# ADC5G_POWER.net
KiCad netlist of a schematic drawn in Altium Designer
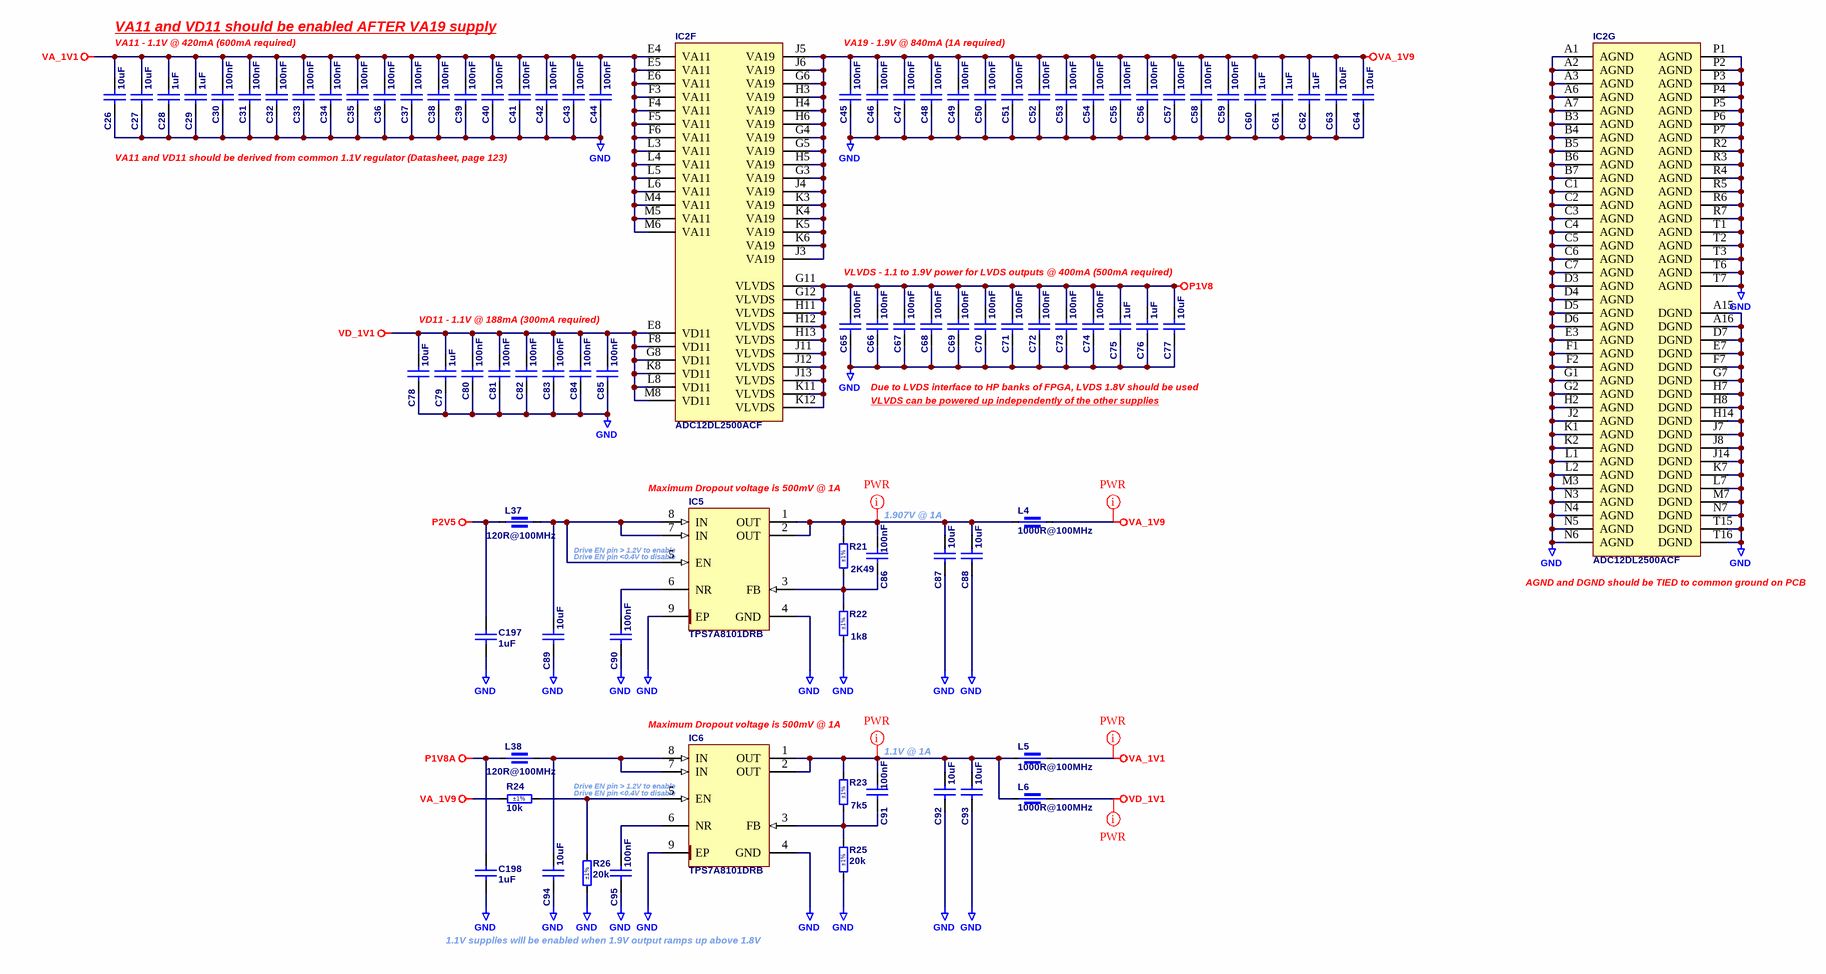
[diagram p0: ADC5G_POWER.SchDoc]

(export (version "E")
  (design (tool "Eeschema 10.0.6"))
  (components
    (comp (ref "C26")
      (value "10uF")
      (footprint "CAPC1608X90N")
      (description "Non-polarised capacitor")
      (fields
        (field (name "PART NUMBER") "CC0603_10UF_16V_10%_X5R_MURATA_GRT188R61C106KE13")
        (field (name "VOLTAGE") "16V")
        (field (name "AUTHOR") "CERN DEM HF")
      )
      (libsource (lib "Capacitors") (part "Capacitor - non polarized"))
    )
    (comp (ref "C27")
      (value "10uF")
      (footprint "CAPC1608X90N")
      (description "Non-polarised capacitor")
      (fields
        (field (name "PART NUMBER") "CC0603_10UF_16V_10%_X5R_MURATA_GRT188R61C106KE13")
        (field (name "VOLTAGE") "16V")
        (field (name "AUTHOR") "CERN DEM HF")
      )
      (libsource (lib "Capacitors") (part "Capacitor - non polarized"))
    )
    (comp (ref "C28")
      (value "1uF")
      (footprint "CAPC1005X55N")
      (description "Non-polarised capacitor")
      (fields
        (field (name "PART NUMBER") "CC0402_1UF_16V_10%_X5R")
        (field (name "VOLTAGE") "16V")
        (field (name "AUTHOR") "CERN DEM JLC")
      )
      (libsource (lib "Capacitors") (part "Capacitor - non polarized"))
    )
    (comp (ref "C29")
      (value "1uF")
      (footprint "CAPC1005X55N")
      (description "Non-polarised capacitor")
      (fields
        (field (name "PART NUMBER") "CC0402_1UF_16V_10%_X5R")
        (field (name "VOLTAGE") "16V")
        (field (name "AUTHOR") "CERN DEM JLC")
      )
      (libsource (lib "Capacitors") (part "Capacitor - non polarized"))
    )
    (comp (ref "C30")
      (value "100nF")
      (footprint "CAPC0603X33N")
      (description "Non-polarised capacitor")
      (fields
        (field (name "PART NUMBER") "CC0201_100NF_6.3V_10%_X7R")
        (field (name "VOLTAGE") "6.3V")
        (field (name "AUTHOR") "CERN DEM BC")
      )
      (libsource (lib "Capacitors") (part "Capacitor - non polarized"))
    )
    (comp (ref "C31")
      (value "100nF")
      (footprint "CAPC0603X33N")
      (description "Non-polarised capacitor")
      (fields
        (field (name "PART NUMBER") "CC0201_100NF_6.3V_10%_X7R")
        (field (name "VOLTAGE") "6.3V")
        (field (name "AUTHOR") "CERN DEM BC")
      )
      (libsource (lib "Capacitors") (part "Capacitor - non polarized"))
    )
    (comp (ref "C32")
      (value "100nF")
      (footprint "CAPC0603X33N")
      (description "Non-polarised capacitor")
      (fields
        (field (name "PART NUMBER") "CC0201_100NF_6.3V_10%_X7R")
        (field (name "VOLTAGE") "6.3V")
        (field (name "AUTHOR") "CERN DEM BC")
      )
      (libsource (lib "Capacitors") (part "Capacitor - non polarized"))
    )
    (comp (ref "C33")
      (value "100nF")
      (footprint "CAPC0603X33N")
      (description "Non-polarised capacitor")
      (fields
        (field (name "PART NUMBER") "CC0201_100NF_6.3V_10%_X7R")
        (field (name "VOLTAGE") "6.3V")
        (field (name "AUTHOR") "CERN DEM BC")
      )
      (libsource (lib "Capacitors") (part "Capacitor - non polarized"))
    )
    (comp (ref "C34")
      (value "100nF")
      (footprint "CAPC0603X33N")
      (description "Non-polarised capacitor")
      (fields
        (field (name "PART NUMBER") "CC0201_100NF_6.3V_10%_X7R")
        (field (name "VOLTAGE") "6.3V")
        (field (name "AUTHOR") "CERN DEM BC")
      )
      (libsource (lib "Capacitors") (part "Capacitor - non polarized"))
    )
    (comp (ref "C35")
      (value "100nF")
      (footprint "CAPC0603X33N")
      (description "Non-polarised capacitor")
      (fields
        (field (name "PART NUMBER") "CC0201_100NF_6.3V_10%_X7R")
        (field (name "VOLTAGE") "6.3V")
        (field (name "AUTHOR") "CERN DEM BC")
      )
      (libsource (lib "Capacitors") (part "Capacitor - non polarized"))
    )
    (comp (ref "C36")
      (value "100nF")
      (footprint "CAPC0603X33N")
      (description "Non-polarised capacitor")
      (fields
        (field (name "PART NUMBER") "CC0201_100NF_6.3V_10%_X7R")
        (field (name "VOLTAGE") "6.3V")
        (field (name "AUTHOR") "CERN DEM BC")
      )
      (libsource (lib "Capacitors") (part "Capacitor - non polarized"))
    )
    (comp (ref "C37")
      (value "100nF")
      (footprint "CAPC0603X33N")
      (description "Non-polarised capacitor")
      (fields
        (field (name "PART NUMBER") "CC0201_100NF_6.3V_10%_X7R")
        (field (name "VOLTAGE") "6.3V")
        (field (name "AUTHOR") "CERN DEM BC")
      )
      (libsource (lib "Capacitors") (part "Capacitor - non polarized"))
    )
    (comp (ref "C38")
      (value "100nF")
      (footprint "CAPC0603X33N")
      (description "Non-polarised capacitor")
      (fields
        (field (name "PART NUMBER") "CC0201_100NF_6.3V_10%_X7R")
        (field (name "VOLTAGE") "6.3V")
        (field (name "AUTHOR") "CERN DEM BC")
      )
      (libsource (lib "Capacitors") (part "Capacitor - non polarized"))
    )
    (comp (ref "C39")
      (value "100nF")
      (footprint "CAPC0603X33N")
      (description "Non-polarised capacitor")
      (fields
        (field (name "PART NUMBER") "CC0201_100NF_6.3V_10%_X7R")
        (field (name "VOLTAGE") "6.3V")
        (field (name "AUTHOR") "CERN DEM BC")
      )
      (libsource (lib "Capacitors") (part "Capacitor - non polarized"))
    )
    (comp (ref "C40")
      (value "100nF")
      (footprint "CAPC0603X33N")
      (description "Non-polarised capacitor")
      (fields
        (field (name "PART NUMBER") "CC0201_100NF_6.3V_10%_X7R")
        (field (name "VOLTAGE") "6.3V")
        (field (name "AUTHOR") "CERN DEM BC")
      )
      (libsource (lib "Capacitors") (part "Capacitor - non polarized"))
    )
    (comp (ref "C41")
      (value "100nF")
      (footprint "CAPC0603X33N")
      (description "Non-polarised capacitor")
      (fields
        (field (name "PART NUMBER") "CC0201_100NF_6.3V_10%_X7R")
        (field (name "VOLTAGE") "6.3V")
        (field (name "AUTHOR") "CERN DEM BC")
      )
      (libsource (lib "Capacitors") (part "Capacitor - non polarized"))
    )
    (comp (ref "C42")
      (value "100nF")
      (footprint "CAPC0603X33N")
      (description "Non-polarised capacitor")
      (fields
        (field (name "PART NUMBER") "CC0201_100NF_6.3V_10%_X7R")
        (field (name "VOLTAGE") "6.3V")
        (field (name "AUTHOR") "CERN DEM BC")
      )
      (libsource (lib "Capacitors") (part "Capacitor - non polarized"))
    )
    (comp (ref "C43")
      (value "100nF")
      (footprint "CAPC0603X33N")
      (description "Non-polarised capacitor")
      (fields
        (field (name "PART NUMBER") "CC0201_100NF_6.3V_10%_X7R")
        (field (name "VOLTAGE") "6.3V")
        (field (name "AUTHOR") "CERN DEM BC")
      )
      (libsource (lib "Capacitors") (part "Capacitor - non polarized"))
    )
    (comp (ref "C44")
      (value "100nF")
      (footprint "CAPC0603X33N")
      (description "Non-polarised capacitor")
      (fields
        (field (name "PART NUMBER") "CC0201_100NF_6.3V_10%_X7R")
        (field (name "VOLTAGE") "6.3V")
        (field (name "AUTHOR") "CERN DEM BC")
      )
      (libsource (lib "Capacitors") (part "Capacitor - non polarized"))
    )
    (comp (ref "C45")
      (value "100nF")
      (footprint "CAPC0603X33N")
      (description "Non-polarised capacitor")
      (fields
        (field (name "PART NUMBER") "CC0201_100NF_6.3V_10%_X7R")
        (field (name "VOLTAGE") "6.3V")
        (field (name "AUTHOR") "CERN DEM BC")
      )
      (libsource (lib "Capacitors") (part "Capacitor - non polarized"))
    )
    (comp (ref "C46")
      (value "100nF")
      (footprint "CAPC0603X33N")
      (description "Non-polarised capacitor")
      (fields
        (field (name "PART NUMBER") "CC0201_100NF_6.3V_10%_X7R")
        (field (name "VOLTAGE") "6.3V")
        (field (name "AUTHOR") "CERN DEM BC")
      )
      (libsource (lib "Capacitors") (part "Capacitor - non polarized"))
    )
    (comp (ref "C47")
      (value "100nF")
      (footprint "CAPC0603X33N")
      (description "Non-polarised capacitor")
      (fields
        (field (name "PART NUMBER") "CC0201_100NF_6.3V_10%_X7R")
        (field (name "VOLTAGE") "6.3V")
        (field (name "AUTHOR") "CERN DEM BC")
      )
      (libsource (lib "Capacitors") (part "Capacitor - non polarized"))
    )
    (comp (ref "C48")
      (value "100nF")
      (footprint "CAPC0603X33N")
      (description "Non-polarised capacitor")
      (fields
        (field (name "PART NUMBER") "CC0201_100NF_6.3V_10%_X7R")
        (field (name "VOLTAGE") "6.3V")
        (field (name "AUTHOR") "CERN DEM BC")
      )
      (libsource (lib "Capacitors") (part "Capacitor - non polarized"))
    )
    (comp (ref "C49")
      (value "100nF")
      (footprint "CAPC0603X33N")
      (description "Non-polarised capacitor")
      (fields
        (field (name "PART NUMBER") "CC0201_100NF_6.3V_10%_X7R")
        (field (name "VOLTAGE") "6.3V")
        (field (name "AUTHOR") "CERN DEM BC")
      )
      (libsource (lib "Capacitors") (part "Capacitor - non polarized"))
    )
    (comp (ref "C50")
      (value "100nF")
      (footprint "CAPC0603X33N")
      (description "Non-polarised capacitor")
      (fields
        (field (name "PART NUMBER") "CC0201_100NF_6.3V_10%_X7R")
        (field (name "VOLTAGE") "6.3V")
        (field (name "AUTHOR") "CERN DEM BC")
      )
      (libsource (lib "Capacitors") (part "Capacitor - non polarized"))
    )
    (comp (ref "C51")
      (value "100nF")
      (footprint "CAPC0603X33N")
      (description "Non-polarised capacitor")
      (fields
        (field (name "PART NUMBER") "CC0201_100NF_6.3V_10%_X7R")
        (field (name "VOLTAGE") "6.3V")
        (field (name "AUTHOR") "CERN DEM BC")
      )
      (libsource (lib "Capacitors") (part "Capacitor - non polarized"))
    )
    (comp (ref "C52")
      (value "100nF")
      (footprint "CAPC0603X33N")
      (description "Non-polarised capacitor")
      (fields
        (field (name "PART NUMBER") "CC0201_100NF_6.3V_10%_X7R")
        (field (name "VOLTAGE") "6.3V")
        (field (name "AUTHOR") "CERN DEM BC")
      )
      (libsource (lib "Capacitors") (part "Capacitor - non polarized"))
    )
    (comp (ref "C53")
      (value "100nF")
      (footprint "CAPC0603X33N")
      (description "Non-polarised capacitor")
      (fields
        (field (name "PART NUMBER") "CC0201_100NF_6.3V_10%_X7R")
        (field (name "VOLTAGE") "6.3V")
        (field (name "AUTHOR") "CERN DEM BC")
      )
      (libsource (lib "Capacitors") (part "Capacitor - non polarized"))
    )
    (comp (ref "C54")
      (value "100nF")
      (footprint "CAPC0603X33N")
      (description "Non-polarised capacitor")
      (fields
        (field (name "PART NUMBER") "CC0201_100NF_6.3V_10%_X7R")
        (field (name "VOLTAGE") "6.3V")
        (field (name "AUTHOR") "CERN DEM BC")
      )
      (libsource (lib "Capacitors") (part "Capacitor - non polarized"))
    )
    (comp (ref "C55")
      (value "100nF")
      (footprint "CAPC0603X33N")
      (description "Non-polarised capacitor")
      (fields
        (field (name "PART NUMBER") "CC0201_100NF_6.3V_10%_X7R")
        (field (name "VOLTAGE") "6.3V")
        (field (name "AUTHOR") "CERN DEM BC")
      )
      (libsource (lib "Capacitors") (part "Capacitor - non polarized"))
    )
    (comp (ref "C56")
      (value "100nF")
      (footprint "CAPC0603X33N")
      (description "Non-polarised capacitor")
      (fields
        (field (name "PART NUMBER") "CC0201_100NF_6.3V_10%_X7R")
        (field (name "VOLTAGE") "6.3V")
        (field (name "AUTHOR") "CERN DEM BC")
      )
      (libsource (lib "Capacitors") (part "Capacitor - non polarized"))
    )
    (comp (ref "C57")
      (value "100nF")
      (footprint "CAPC0603X33N")
      (description "Non-polarised capacitor")
      (fields
        (field (name "PART NUMBER") "CC0201_100NF_6.3V_10%_X7R")
        (field (name "VOLTAGE") "6.3V")
        (field (name "AUTHOR") "CERN DEM BC")
      )
      (libsource (lib "Capacitors") (part "Capacitor - non polarized"))
    )
    (comp (ref "C58")
      (value "100nF")
      (footprint "CAPC0603X33N")
      (description "Non-polarised capacitor")
      (fields
        (field (name "PART NUMBER") "CC0201_100NF_6.3V_10%_X7R")
        (field (name "VOLTAGE") "6.3V")
        (field (name "AUTHOR") "CERN DEM BC")
      )
      (libsource (lib "Capacitors") (part "Capacitor - non polarized"))
    )
    (comp (ref "C59")
      (value "100nF")
      (footprint "CAPC0603X33N")
      (description "Non-polarised capacitor")
      (fields
        (field (name "PART NUMBER") "CC0201_100NF_6.3V_10%_X7R")
        (field (name "VOLTAGE") "6.3V")
        (field (name "AUTHOR") "CERN DEM BC")
      )
      (libsource (lib "Capacitors") (part "Capacitor - non polarized"))
    )
    (comp (ref "C60")
      (value "1uF")
      (footprint "CAPC1005X55N")
      (description "Non-polarised capacitor")
      (fields
        (field (name "PART NUMBER") "CC0402_1UF_16V_10%_X5R")
        (field (name "VOLTAGE") "16V")
        (field (name "AUTHOR") "CERN DEM JLC")
      )
      (libsource (lib "Capacitors") (part "Capacitor - non polarized"))
    )
    (comp (ref "C61")
      (value "1uF")
      (footprint "CAPC1005X55N")
      (description "Non-polarised capacitor")
      (fields
        (field (name "PART NUMBER") "CC0402_1UF_16V_10%_X5R")
        (field (name "VOLTAGE") "16V")
        (field (name "AUTHOR") "CERN DEM JLC")
      )
      (libsource (lib "Capacitors") (part "Capacitor - non polarized"))
    )
    (comp (ref "C62")
      (value "1uF")
      (footprint "CAPC1005X55N")
      (description "Non-polarised capacitor")
      (fields
        (field (name "PART NUMBER") "CC0402_1UF_16V_10%_X5R")
        (field (name "VOLTAGE") "16V")
        (field (name "AUTHOR") "CERN DEM JLC")
      )
      (libsource (lib "Capacitors") (part "Capacitor - non polarized"))
    )
    (comp (ref "C63")
      (value "10uF")
      (footprint "CAPC1608X90N")
      (description "Non-polarised capacitor")
      (fields
        (field (name "PART NUMBER") "CC0603_10UF_16V_10%_X5R_MURATA_GRT188R61C106KE13")
        (field (name "VOLTAGE") "16V")
        (field (name "AUTHOR") "CERN DEM HF")
      )
      (libsource (lib "Capacitors") (part "Capacitor - non polarized"))
    )
    (comp (ref "C64")
      (value "10uF")
      (footprint "CAPC1608X90N")
      (description "Non-polarised capacitor")
      (fields
        (field (name "PART NUMBER") "CC0603_10UF_16V_10%_X5R_MURATA_GRT188R61C106KE13")
        (field (name "VOLTAGE") "16V")
        (field (name "AUTHOR") "CERN DEM HF")
      )
      (libsource (lib "Capacitors") (part "Capacitor - non polarized"))
    )
    (comp (ref "C65")
      (value "100nF")
      (footprint "CAPC0603X33N")
      (description "Non-polarised capacitor")
      (fields
        (field (name "PART NUMBER") "CC0201_100NF_6.3V_10%_X7R")
        (field (name "VOLTAGE") "6.3V")
        (field (name "AUTHOR") "CERN DEM BC")
      )
      (libsource (lib "Capacitors") (part "Capacitor - non polarized"))
    )
    (comp (ref "C66")
      (value "100nF")
      (footprint "CAPC0603X33N")
      (description "Non-polarised capacitor")
      (fields
        (field (name "PART NUMBER") "CC0201_100NF_6.3V_10%_X7R")
        (field (name "VOLTAGE") "6.3V")
        (field (name "AUTHOR") "CERN DEM BC")
      )
      (libsource (lib "Capacitors") (part "Capacitor - non polarized"))
    )
    (comp (ref "C67")
      (value "100nF")
      (footprint "CAPC0603X33N")
      (description "Non-polarised capacitor")
      (fields
        (field (name "PART NUMBER") "CC0201_100NF_6.3V_10%_X7R")
        (field (name "VOLTAGE") "6.3V")
        (field (name "AUTHOR") "CERN DEM BC")
      )
      (libsource (lib "Capacitors") (part "Capacitor - non polarized"))
    )
    (comp (ref "C68")
      (value "100nF")
      (footprint "CAPC0603X33N")
      (description "Non-polarised capacitor")
      (fields
        (field (name "PART NUMBER") "CC0201_100NF_6.3V_10%_X7R")
        (field (name "VOLTAGE") "6.3V")
        (field (name "AUTHOR") "CERN DEM BC")
      )
      (libsource (lib "Capacitors") (part "Capacitor - non polarized"))
    )
    (comp (ref "C69")
      (value "100nF")
      (footprint "CAPC0603X33N")
      (description "Non-polarised capacitor")
      (fields
        (field (name "PART NUMBER") "CC0201_100NF_6.3V_10%_X7R")
        (field (name "VOLTAGE") "6.3V")
        (field (name "AUTHOR") "CERN DEM BC")
      )
      (libsource (lib "Capacitors") (part "Capacitor - non polarized"))
    )
    (comp (ref "C70")
      (value "100nF")
      (footprint "CAPC0603X33N")
      (description "Non-polarised capacitor")
      (fields
        (field (name "PART NUMBER") "CC0201_100NF_6.3V_10%_X7R")
        (field (name "VOLTAGE") "6.3V")
        (field (name "AUTHOR") "CERN DEM BC")
      )
      (libsource (lib "Capacitors") (part "Capacitor - non polarized"))
    )
    (comp (ref "C71")
      (value "100nF")
      (footprint "CAPC0603X33N")
      (description "Non-polarised capacitor")
      (fields
        (field (name "PART NUMBER") "CC0201_100NF_6.3V_10%_X7R")
        (field (name "VOLTAGE") "6.3V")
        (field (name "AUTHOR") "CERN DEM BC")
      )
      (libsource (lib "Capacitors") (part "Capacitor - non polarized"))
    )
    (comp (ref "C72")
      (value "100nF")
      (footprint "CAPC0603X33N")
      (description "Non-polarised capacitor")
      (fields
        (field (name "PART NUMBER") "CC0201_100NF_6.3V_10%_X7R")
        (field (name "VOLTAGE") "6.3V")
        (field (name "AUTHOR") "CERN DEM BC")
      )
      (libsource (lib "Capacitors") (part "Capacitor - non polarized"))
    )
    (comp (ref "C73")
      (value "100nF")
      (footprint "CAPC0603X33N")
      (description "Non-polarised capacitor")
      (fields
        (field (name "PART NUMBER") "CC0201_100NF_6.3V_10%_X7R")
        (field (name "VOLTAGE") "6.3V")
        (field (name "AUTHOR") "CERN DEM BC")
      )
      (libsource (lib "Capacitors") (part "Capacitor - non polarized"))
    )
    (comp (ref "C74")
      (value "100nF")
      (footprint "CAPC0603X33N")
      (description "Non-polarised capacitor")
      (fields
        (field (name "PART NUMBER") "CC0201_100NF_6.3V_10%_X7R")
        (field (name "VOLTAGE") "6.3V")
        (field (name "AUTHOR") "CERN DEM BC")
      )
      (libsource (lib "Capacitors") (part "Capacitor - non polarized"))
    )
    (comp (ref "C75")
      (value "1uF")
      (footprint "CAPC1005X55N")
      (description "Non-polarised capacitor")
      (fields
        (field (name "PART NUMBER") "CC0402_1UF_16V_10%_X5R")
        (field (name "VOLTAGE") "16V")
        (field (name "AUTHOR") "CERN DEM JLC")
      )
      (libsource (lib "Capacitors") (part "Capacitor - non polarized"))
    )
    (comp (ref "C76")
      (value "1uF")
      (footprint "CAPC1005X55N")
      (description "Non-polarised capacitor")
      (fields
        (field (name "PART NUMBER") "CC0402_1UF_16V_10%_X5R")
        (field (name "VOLTAGE") "16V")
        (field (name "AUTHOR") "CERN DEM JLC")
      )
      (libsource (lib "Capacitors") (part "Capacitor - non polarized"))
    )
    (comp (ref "C77")
      (value "10uF")
      (footprint "CAPC1608X90N")
      (description "Non-polarised capacitor")
      (fields
        (field (name "PART NUMBER") "CC0603_10UF_16V_10%_X5R_MURATA_GRT188R61C106KE13")
        (field (name "VOLTAGE") "16V")
        (field (name "AUTHOR") "CERN DEM HF")
      )
      (libsource (lib "Capacitors") (part "Capacitor - non polarized"))
    )
    (comp (ref "C78")
      (value "10uF")
      (footprint "CAPC1608X90N")
      (description "Non-polarised capacitor")
      (fields
        (field (name "PART NUMBER") "CC0603_10UF_16V_10%_X5R_MURATA_GRT188R61C106KE13")
        (field (name "VOLTAGE") "16V")
        (field (name "AUTHOR") "CERN DEM HF")
      )
      (libsource (lib "Capacitors") (part "Capacitor - non polarized"))
    )
    (comp (ref "C79")
      (value "1uF")
      (footprint "CAPC1005X55N")
      (description "Non-polarised capacitor")
      (fields
        (field (name "PART NUMBER") "CC0402_1UF_16V_10%_X5R")
        (field (name "VOLTAGE") "16V")
        (field (name "AUTHOR") "CERN DEM JLC")
      )
      (libsource (lib "Capacitors") (part "Capacitor - non polarized"))
    )
    (comp (ref "C80")
      (value "100nF")
      (footprint "CAPC0603X33N")
      (description "Non-polarised capacitor")
      (fields
        (field (name "PART NUMBER") "CC0201_100NF_6.3V_10%_X7R")
        (field (name "VOLTAGE") "6.3V")
        (field (name "AUTHOR") "CERN DEM BC")
      )
      (libsource (lib "Capacitors") (part "Capacitor - non polarized"))
    )
    (comp (ref "C81")
      (value "100nF")
      (footprint "CAPC0603X33N")
      (description "Non-polarised capacitor")
      (fields
        (field (name "PART NUMBER") "CC0201_100NF_6.3V_10%_X7R")
        (field (name "VOLTAGE") "6.3V")
        (field (name "AUTHOR") "CERN DEM BC")
      )
      (libsource (lib "Capacitors") (part "Capacitor - non polarized"))
    )
    (comp (ref "C82")
      (value "100nF")
      (footprint "CAPC0603X33N")
      (description "Non-polarised capacitor")
      (fields
        (field (name "PART NUMBER") "CC0201_100NF_6.3V_10%_X7R")
        (field (name "VOLTAGE") "6.3V")
        (field (name "AUTHOR") "CERN DEM BC")
      )
      (libsource (lib "Capacitors") (part "Capacitor - non polarized"))
    )
    (comp (ref "C83")
      (value "100nF")
      (footprint "CAPC0603X33N")
      (description "Non-polarised capacitor")
      (fields
        (field (name "PART NUMBER") "CC0201_100NF_6.3V_10%_X7R")
        (field (name "VOLTAGE") "6.3V")
        (field (name "AUTHOR") "CERN DEM BC")
      )
      (libsource (lib "Capacitors") (part "Capacitor - non polarized"))
    )
    (comp (ref "C84")
      (value "100nF")
      (footprint "CAPC0603X33N")
      (description "Non-polarised capacitor")
      (fields
        (field (name "PART NUMBER") "CC0201_100NF_6.3V_10%_X7R")
        (field (name "VOLTAGE") "6.3V")
        (field (name "AUTHOR") "CERN DEM BC")
      )
      (libsource (lib "Capacitors") (part "Capacitor - non polarized"))
    )
    (comp (ref "C85")
      (value "100nF")
      (footprint "CAPC0603X33N")
      (description "Non-polarised capacitor")
      (fields
        (field (name "PART NUMBER") "CC0201_100NF_6.3V_10%_X7R")
        (field (name "VOLTAGE") "6.3V")
        (field (name "AUTHOR") "CERN DEM BC")
      )
      (libsource (lib "Capacitors") (part "Capacitor - non polarized"))
    )
    (comp (ref "C86")
      (value "100nF")
      (footprint "CAPC1005X55N")
      (description "Non-polarised capacitor")
      (fields
        (field (name "PART NUMBER") "CC0402_100NF_16V_10%_X5R")
        (field (name "VOLTAGE") "16V")
        (field (name "AUTHOR") "CERN DEM JLC")
      )
      (libsource (lib "Capacitors") (part "Capacitor - non polarized"))
    )
    (comp (ref "C87")
      (value "10uF")
      (footprint "CAPC1608X90N")
      (description "Non-polarised capacitor")
      (fields
        (field (name "PART NUMBER") "CC0603_10UF_16V_10%_X5R_MURATA_GRT188R61C106KE13")
        (field (name "VOLTAGE") "16V")
        (field (name "AUTHOR") "CERN DEM HF")
      )
      (libsource (lib "Capacitors") (part "Capacitor - non polarized"))
    )
    (comp (ref "C88")
      (value "10uF")
      (footprint "CAPC1608X90N")
      (description "Non-polarised capacitor")
      (fields
        (field (name "PART NUMBER") "CC0603_10UF_16V_10%_X5R_MURATA_GRT188R61C106KE13")
        (field (name "VOLTAGE") "16V")
        (field (name "AUTHOR") "CERN DEM HF")
      )
      (libsource (lib "Capacitors") (part "Capacitor - non polarized"))
    )
    (comp (ref "C89")
      (value "10uF")
      (footprint "CAPC1608X90N")
      (description "Non-polarised capacitor")
      (fields
        (field (name "PART NUMBER") "CC0603_10UF_16V_10%_X5R_MURATA_GRT188R61C106KE13")
        (field (name "VOLTAGE") "16V")
        (field (name "AUTHOR") "CERN DEM HF")
      )
      (libsource (lib "Capacitors") (part "Capacitor - non polarized"))
    )
    (comp (ref "C90")
      (value "100nF")
      (footprint "CAPC1005X55N")
      (description "Non-polarised capacitor")
      (fields
        (field (name "PART NUMBER") "CC0402_100NF_16V_10%_X5R")
        (field (name "VOLTAGE") "16V")
        (field (name "AUTHOR") "CERN DEM JLC")
      )
      (libsource (lib "Capacitors") (part "Capacitor - non polarized"))
    )
    (comp (ref "C91")
      (value "100nF")
      (footprint "CAPC1005X55N")
      (description "Non-polarised capacitor")
      (fields
        (field (name "PART NUMBER") "CC0402_100NF_16V_10%_X5R")
        (field (name "VOLTAGE") "16V")
        (field (name "AUTHOR") "CERN DEM JLC")
      )
      (libsource (lib "Capacitors") (part "Capacitor - non polarized"))
    )
    (comp (ref "C92")
      (value "10uF")
      (footprint "CAPC1608X90N")
      (description "Non-polarised capacitor")
      (fields
        (field (name "PART NUMBER") "CC0603_10UF_16V_10%_X5R_MURATA_GRT188R61C106KE13")
        (field (name "VOLTAGE") "16V")
        (field (name "AUTHOR") "CERN DEM HF")
      )
      (libsource (lib "Capacitors") (part "Capacitor - non polarized"))
    )
    (comp (ref "C93")
      (value "10uF")
      (footprint "CAPC1608X90N")
      (description "Non-polarised capacitor")
      (fields
        (field (name "PART NUMBER") "CC0603_10UF_16V_10%_X5R_MURATA_GRT188R61C106KE13")
        (field (name "VOLTAGE") "16V")
        (field (name "AUTHOR") "CERN DEM HF")
      )
      (libsource (lib "Capacitors") (part "Capacitor - non polarized"))
    )
    (comp (ref "C94")
      (value "10uF")
      (footprint "CAPC1608X90N")
      (description "Non-polarised capacitor")
      (fields
        (field (name "PART NUMBER") "CC0603_10UF_16V_10%_X5R_MURATA_GRT188R61C106KE13")
        (field (name "VOLTAGE") "16V")
        (field (name "AUTHOR") "CERN DEM HF")
      )
      (libsource (lib "Capacitors") (part "Capacitor - non polarized"))
    )
    (comp (ref "C95")
      (value "100nF")
      (footprint "CAPC1005X55N")
      (description "Non-polarised capacitor")
      (fields
        (field (name "PART NUMBER") "CC0402_100NF_16V_10%_X5R")
        (field (name "VOLTAGE") "16V")
        (field (name "AUTHOR") "CERN DEM JLC")
      )
      (libsource (lib "Capacitors") (part "Capacitor - non polarized"))
    )
    (comp (ref "C197")
      (value "1uF")
      (footprint "CAPC1005X55N")
      (description "Non-polarised capacitor")
      (fields
        (field (name "PART NUMBER") "CC0402_1UF_25V_10%_X5R")
        (field (name "VOLTAGE") "25V")
        (field (name "AUTHOR") "CERN DEM BC")
      )
      (libsource (lib "Capacitors") (part "Capacitor - non polarized"))
    )
    (comp (ref "C198")
      (value "1uF")
      (footprint "CAPC1005X55N")
      (description "Non-polarised capacitor")
      (fields
        (field (name "PART NUMBER") "CC0402_1UF_25V_10%_X5R")
        (field (name "VOLTAGE") "25V")
        (field (name "AUTHOR") "CERN DEM BC")
      )
      (libsource (lib "Capacitors") (part "Capacitor - non polarized"))
    )
    (comp (ref "IC2")
      (value "ADC12DL2500ACF")
      (footprint "BGA256C100P16X16_1700X1700X331")
      (description "Single-Supply, Multichannel, 125kSPS, 24-Bit, Sigma-Delta ADC with ±10V Inputs")
      (fields (field (name "MANUFACTURER") "TEXAS INSTRUMENTS") (field (name "AUTHOR") "CERN DEM HF"))
      (libsource (lib "ICs And Semiconductors") (part "ADC12DLX500ACF"))
    )
    (comp (ref "IC5")
      (value "TPS7A8101DRB")
      (footprint "TEXAS_DRB(S-PVSON-N8)")
      (description "0.8V to 6V, 1A, Low-Noise, Wide-Bandwidth, High PSRR, Low-Dropout Linear Regulator")
      (fields (field (name "MANUFACTURER") "TEXAS INSTRUMENTS") (field (name "AUTHOR") "CERN DEM BC"))
      (libsource (lib "ICs And Semiconductors") (part "TPS7A8101DRB"))
    )
    (comp (ref "IC6")
      (value "TPS7A8101DRB")
      (footprint "TEXAS_DRB(S-PVSON-N8)")
      (description "0.8V to 6V, 1A, Low-Noise, Wide-Bandwidth, High PSRR, Low-Dropout Linear Regulator")
      (fields (field (name "MANUFACTURER") "TEXAS INSTRUMENTS") (field (name "AUTHOR") "CERN DEM BC"))
      (libsource (lib "ICs And Semiconductors") (part "TPS7A8101DRB"))
    )
    (comp (ref "L4")
      (value "1000R@100MHz")
      (footprint "INDC1608X95N")
      (fields
        (field (name "PART NUMBER") "IND0603_MURATA_BLM18KG102SN1")
        (field (name "POWER") "1A")
        (field (name "TOLERANCE") "±25%")
        (field (name "AUTHOR") "CERN DEM HF")
      )
      (libsource (lib "Inductors & Transformers") (part "Ferrite Bead"))
    )
    (comp (ref "L5")
      (value "1000R@100MHz")
      (footprint "INDC1608X95N")
      (fields
        (field (name "PART NUMBER") "IND0603_MURATA_BLM18KG102SN1")
        (field (name "POWER") "1A")
        (field (name "TOLERANCE") "±25%")
        (field (name "AUTHOR") "CERN DEM HF")
      )
      (libsource (lib "Inductors & Transformers") (part "Ferrite Bead"))
    )
    (comp (ref "L6")
      (value "1000R@100MHz")
      (footprint "INDC1608X95N")
      (fields
        (field (name "PART NUMBER") "IND0603_MURATA_BLM18KG102SN1")
        (field (name "POWER") "1A")
        (field (name "TOLERANCE") "±25%")
        (field (name "AUTHOR") "CERN DEM HF")
      )
      (libsource (lib "Inductors & Transformers") (part "Ferrite Bead"))
    )
    (comp (ref "L37")
      (value "120R@100MHz")
      (footprint "INDC1005X55N")
      (fields
        (field (name "PART NUMBER") "IND0402_MURATA_BLM15PX121SN1D")
        (field (name "POWER") "2A")
        (field (name "TOLERANCE") "±25%")
        (field (name "AUTHOR") "CERN DEM JMW")
      )
      (libsource (lib "Inductors & Transformers") (part "Ferrite Bead"))
    )
    (comp (ref "L38")
      (value "120R@100MHz")
      (footprint "INDC1005X55N")
      (fields
        (field (name "PART NUMBER") "IND0402_MURATA_BLM15PX121SN1D")
        (field (name "POWER") "2A")
        (field (name "TOLERANCE") "±25%")
        (field (name "AUTHOR") "CERN DEM JMW")
      )
      (libsource (lib "Inductors & Transformers") (part "Ferrite Bead"))
    )
    (comp (ref "R21")
      (value "2K49")
      (footprint "RESC1005X40N")
      (description "Resistor - 1%")
      (fields
        (field (name "TOLERANCE") "±1%")
        (field (name "PART NUMBER") "R0402_2K49_1%_0.063W_100PPM")
        (field (name "POWER") "0.063W")
        (field (name "AUTHOR") "CERN DEM BC")
      )
      (libsource (lib "Resistors") (part "Resistor - 1%"))
    )
    (comp (ref "R22")
      (value "1k8")
      (footprint "RESC1005X40N")
      (description "Resistor - 1%")
      (fields
        (field (name "TOLERANCE") "±1%")
        (field (name "PART NUMBER") "R0402_1K8_1%_0.0625W_100PPM")
        (field (name "POWER") "0.0625W")
        (field (name "AUTHOR") "CERN DEM JLC")
      )
      (libsource (lib "Resistors") (part "Resistor - 1%"))
    )
    (comp (ref "R23")
      (value "7k5")
      (footprint "RESC1005X40N")
      (description "Resistor - 1%")
      (fields
        (field (name "TOLERANCE") "±1%")
        (field (name "PART NUMBER") "R0402_7K5_1%_0.0625W_100PPM")
        (field (name "POWER") "0.0625W")
        (field (name "AUTHOR") "CERN DEM JLC")
      )
      (libsource (lib "Resistors") (part "Resistor - 1%"))
    )
    (comp (ref "R24")
      (value "10k")
      (footprint "RESC1005X40N")
      (description "Resistor - 1%")
      (fields
        (field (name "TOLERANCE") "±1%")
        (field (name "PART NUMBER") "R0402_10K_1%_0.0625W_100PPM")
        (field (name "POWER") "0.0625W")
        (field (name "AUTHOR") "CERN DEM JLC")
      )
      (libsource (lib "Resistors") (part "Resistor - 1%"))
    )
    (comp (ref "R25")
      (value "20k")
      (footprint "RESC1005X40N")
      (description "Resistor - 1%")
      (fields
        (field (name "TOLERANCE") "±1%")
        (field (name "PART NUMBER") "R0402_20K_1%_0.0625W_100PPM")
        (field (name "POWER") "0.0625W")
        (field (name "AUTHOR") "CERN DEM JLC")
      )
      (libsource (lib "Resistors") (part "Resistor - 1%"))
    )
    (comp (ref "R26")
      (value "20k")
      (footprint "RESC1005X40N")
      (description "Resistor - 1%")
      (fields
        (field (name "TOLERANCE") "±1%")
        (field (name "PART NUMBER") "R0402_20K_1%_0.0625W_100PPM")
        (field (name "POWER") "0.0625W")
        (field (name "AUTHOR") "CERN DEM JLC")
      )
      (libsource (lib "Resistors") (part "Resistor - 1%"))
    )
  )
  (nets
    (net (code "1") (name "GND") (class "Default")
      (node (ref "C197") (pin "1") (pinfunction "1_1") (pintype "passive"))
      (node (ref "C198") (pin "1") (pinfunction "1_1") (pintype "passive"))
      (node (ref "C26") (pin "1") (pinfunction "1_1") (pintype "passive"))
      (node (ref "C27") (pin "1") (pinfunction "1_1") (pintype "passive"))
      (node (ref "C28") (pin "1") (pinfunction "1_1") (pintype "passive"))
      (node (ref "C29") (pin "1") (pinfunction "1_1") (pintype "passive"))
      (node (ref "C30") (pin "1") (pinfunction "1_1") (pintype "passive"))
      (node (ref "C31") (pin "1") (pinfunction "1_1") (pintype "passive"))
      (node (ref "C32") (pin "1") (pinfunction "1_1") (pintype "passive"))
      (node (ref "C33") (pin "1") (pinfunction "1_1") (pintype "passive"))
      (node (ref "C34") (pin "1") (pinfunction "1_1") (pintype "passive"))
      (node (ref "C35") (pin "1") (pinfunction "1_1") (pintype "passive"))
      (node (ref "C36") (pin "1") (pinfunction "1_1") (pintype "passive"))
      (node (ref "C37") (pin "1") (pinfunction "1_1") (pintype "passive"))
      (node (ref "C38") (pin "1") (pinfunction "1_1") (pintype "passive"))
      (node (ref "C39") (pin "1") (pinfunction "1_1") (pintype "passive"))
      (node (ref "C40") (pin "1") (pinfunction "1_1") (pintype "passive"))
      (node (ref "C41") (pin "1") (pinfunction "1_1") (pintype "passive"))
      (node (ref "C42") (pin "1") (pinfunction "1_1") (pintype "passive"))
      (node (ref "C43") (pin "1") (pinfunction "1_1") (pintype "passive"))
      (node (ref "C44") (pin "1") (pinfunction "1_1") (pintype "passive"))
      (node (ref "C45") (pin "1") (pinfunction "1_1") (pintype "passive"))
      (node (ref "C46") (pin "1") (pinfunction "1_1") (pintype "passive"))
      (node (ref "C47") (pin "1") (pinfunction "1_1") (pintype "passive"))
      (node (ref "C48") (pin "1") (pinfunction "1_1") (pintype "passive"))
      (node (ref "C49") (pin "1") (pinfunction "1_1") (pintype "passive"))
      (node (ref "C50") (pin "1") (pinfunction "1_1") (pintype "passive"))
      (node (ref "C51") (pin "1") (pinfunction "1_1") (pintype "passive"))
      (node (ref "C52") (pin "1") (pinfunction "1_1") (pintype "passive"))
      (node (ref "C53") (pin "1") (pinfunction "1_1") (pintype "passive"))
      (node (ref "C54") (pin "1") (pinfunction "1_1") (pintype "passive"))
      (node (ref "C55") (pin "1") (pinfunction "1_1") (pintype "passive"))
      (node (ref "C56") (pin "1") (pinfunction "1_1") (pintype "passive"))
      (node (ref "C57") (pin "1") (pinfunction "1_1") (pintype "passive"))
      (node (ref "C58") (pin "1") (pinfunction "1_1") (pintype "passive"))
      (node (ref "C59") (pin "1") (pinfunction "1_1") (pintype "passive"))
      (node (ref "C60") (pin "1") (pinfunction "1_1") (pintype "passive"))
      (node (ref "C61") (pin "1") (pinfunction "1_1") (pintype "passive"))
      (node (ref "C62") (pin "1") (pinfunction "1_1") (pintype "passive"))
      (node (ref "C63") (pin "1") (pinfunction "1_1") (pintype "passive"))
      (node (ref "C64") (pin "1") (pinfunction "1_1") (pintype "passive"))
      (node (ref "C65") (pin "1") (pinfunction "1_1") (pintype "passive"))
      (node (ref "C66") (pin "1") (pinfunction "1_1") (pintype "passive"))
      (node (ref "C67") (pin "1") (pinfunction "1_1") (pintype "passive"))
      (node (ref "C68") (pin "1") (pinfunction "1_1") (pintype "passive"))
      (node (ref "C69") (pin "1") (pinfunction "1_1") (pintype "passive"))
      (node (ref "C70") (pin "1") (pinfunction "1_1") (pintype "passive"))
      (node (ref "C71") (pin "1") (pinfunction "1_1") (pintype "passive"))
      (node (ref "C72") (pin "1") (pinfunction "1_1") (pintype "passive"))
      (node (ref "C73") (pin "1") (pinfunction "1_1") (pintype "passive"))
      (node (ref "C74") (pin "1") (pinfunction "1_1") (pintype "passive"))
      (node (ref "C75") (pin "1") (pinfunction "1_1") (pintype "passive"))
      (node (ref "C76") (pin "1") (pinfunction "1_1") (pintype "passive"))
      (node (ref "C77") (pin "1") (pinfunction "1_1") (pintype "passive"))
      (node (ref "C78") (pin "1") (pinfunction "1_1") (pintype "passive"))
      (node (ref "C79") (pin "1") (pinfunction "1_1") (pintype "passive"))
      (node (ref "C80") (pin "1") (pinfunction "1_1") (pintype "passive"))
      (node (ref "C81") (pin "1") (pinfunction "1_1") (pintype "passive"))
      (node (ref "C82") (pin "1") (pinfunction "1_1") (pintype "passive"))
      (node (ref "C83") (pin "1") (pinfunction "1_1") (pintype "passive"))
      (node (ref "C84") (pin "1") (pinfunction "1_1") (pintype "passive"))
      (node (ref "C85") (pin "1") (pinfunction "1_1") (pintype "passive"))
      (node (ref "C87") (pin "1") (pinfunction "1_1") (pintype "passive"))
      (node (ref "C88") (pin "1") (pinfunction "1_1") (pintype "passive"))
      (node (ref "C89") (pin "1") (pinfunction "1_1") (pintype "passive"))
      (node (ref "C90") (pin "1") (pinfunction "1_1") (pintype "passive"))
      (node (ref "C92") (pin "1") (pinfunction "1_1") (pintype "passive"))
      (node (ref "C93") (pin "1") (pinfunction "1_1") (pintype "passive"))
      (node (ref "C94") (pin "1") (pinfunction "1_1") (pintype "passive"))
      (node (ref "C95") (pin "1") (pinfunction "1_1") (pintype "passive"))
      (node (ref "IC2") (pin "A1") (pinfunction "AGND_A1") (pintype "power_in"))
      (node (ref "IC2") (pin "A15") (pinfunction "DGND_A15") (pintype "power_in"))
      (node (ref "IC2") (pin "A16") (pinfunction "DGND_A16") (pintype "power_in"))
      (node (ref "IC2") (pin "A2") (pinfunction "AGND_A2") (pintype "power_in"))
      (node (ref "IC2") (pin "A3") (pinfunction "AGND_A3") (pintype "power_in"))
      (node (ref "IC2") (pin "A6") (pinfunction "AGND_A6") (pintype "power_in"))
      (node (ref "IC2") (pin "A7") (pinfunction "AGND_A7") (pintype "power_in"))
      (node (ref "IC2") (pin "B3") (pinfunction "AGND_B3") (pintype "power_in"))
      (node (ref "IC2") (pin "B4") (pinfunction "AGND_B4") (pintype "power_in"))
      (node (ref "IC2") (pin "B5") (pinfunction "AGND_B5") (pintype "power_in"))
      (node (ref "IC2") (pin "B6") (pinfunction "AGND_B6") (pintype "power_in"))
      (node (ref "IC2") (pin "B7") (pinfunction "AGND_B7") (pintype "power_in"))
      (node (ref "IC2") (pin "C1") (pinfunction "AGND_C1") (pintype "power_in"))
      (node (ref "IC2") (pin "C2") (pinfunction "AGND_C2") (pintype "power_in"))
      (node (ref "IC2") (pin "C3") (pinfunction "AGND_C3") (pintype "power_in"))
      (node (ref "IC2") (pin "C4") (pinfunction "AGND_C4") (pintype "power_in"))
      (node (ref "IC2") (pin "C5") (pinfunction "AGND_C5") (pintype "power_in"))
      (node (ref "IC2") (pin "C6") (pinfunction "AGND_C6") (pintype "power_in"))
      (node (ref "IC2") (pin "C7") (pinfunction "AGND_C7") (pintype "power_in"))
      (node (ref "IC2") (pin "D3") (pinfunction "AGND_D3") (pintype "power_in"))
      (node (ref "IC2") (pin "D4") (pinfunction "AGND_D4") (pintype "power_in"))
      (node (ref "IC2") (pin "D5") (pinfunction "AGND_D5") (pintype "power_in"))
      (node (ref "IC2") (pin "D6") (pinfunction "AGND_D6") (pintype "power_in"))
      (node (ref "IC2") (pin "D7") (pinfunction "DGND_D7") (pintype "power_in"))
      (node (ref "IC2") (pin "E3") (pinfunction "AGND_E3") (pintype "power_in"))
      (node (ref "IC2") (pin "E7") (pinfunction "DGND_E7") (pintype "power_in"))
      (node (ref "IC2") (pin "F1") (pinfunction "AGND_F1") (pintype "power_in"))
      (node (ref "IC2") (pin "F2") (pinfunction "AGND_F2") (pintype "power_in"))
      (node (ref "IC2") (pin "F7") (pinfunction "DGND_F7") (pintype "power_in"))
      (node (ref "IC2") (pin "G1") (pinfunction "AGND_G1") (pintype "power_in"))
      (node (ref "IC2") (pin "G2") (pinfunction "AGND_G2") (pintype "power_in"))
      (node (ref "IC2") (pin "G7") (pinfunction "DGND_G7") (pintype "power_in"))
      (node (ref "IC2") (pin "H14") (pinfunction "DGND_H14") (pintype "power_in"))
      (node (ref "IC2") (pin "H2") (pinfunction "AGND_H2") (pintype "power_in"))
      (node (ref "IC2") (pin "H7") (pinfunction "DGND_H7") (pintype "power_in"))
      (node (ref "IC2") (pin "H8") (pinfunction "DGND_H8") (pintype "power_in"))
      (node (ref "IC2") (pin "J14") (pinfunction "DGND_J14") (pintype "power_in"))
      (node (ref "IC2") (pin "J2") (pinfunction "AGND_J2") (pintype "power_in"))
      (node (ref "IC2") (pin "J7") (pinfunction "DGND_J7") (pintype "power_in"))
      (node (ref "IC2") (pin "J8") (pinfunction "DGND_J8") (pintype "power_in"))
      (node (ref "IC2") (pin "K1") (pinfunction "AGND_K1") (pintype "power_in"))
      (node (ref "IC2") (pin "K2") (pinfunction "AGND_K2") (pintype "power_in"))
      (node (ref "IC2") (pin "K7") (pinfunction "DGND_K7") (pintype "power_in"))
      (node (ref "IC2") (pin "L1") (pinfunction "AGND_L1") (pintype "power_in"))
      (node (ref "IC2") (pin "L2") (pinfunction "AGND_L2") (pintype "power_in"))
      (node (ref "IC2") (pin "L7") (pinfunction "DGND_L7") (pintype "power_in"))
      (node (ref "IC2") (pin "M3") (pinfunction "AGND_M3") (pintype "power_in"))
      (node (ref "IC2") (pin "M7") (pinfunction "DGND_M7") (pintype "power_in"))
      (node (ref "IC2") (pin "N3") (pinfunction "AGND_N3") (pintype "power_in"))
      (node (ref "IC2") (pin "N4") (pinfunction "AGND_N4") (pintype "power_in"))
      (node (ref "IC2") (pin "N5") (pinfunction "AGND_N5") (pintype "power_in"))
      (node (ref "IC2") (pin "N6") (pinfunction "AGND_N6") (pintype "power_in"))
      (node (ref "IC2") (pin "N7") (pinfunction "DGND_N7") (pintype "power_in"))
      (node (ref "IC2") (pin "P1") (pinfunction "AGND_P1") (pintype "power_in"))
      (node (ref "IC2") (pin "P2") (pinfunction "AGND_P2") (pintype "power_in"))
      (node (ref "IC2") (pin "P3") (pinfunction "AGND_P3") (pintype "power_in"))
      (node (ref "IC2") (pin "P4") (pinfunction "AGND_P4") (pintype "power_in"))
      (node (ref "IC2") (pin "P5") (pinfunction "AGND_P5") (pintype "power_in"))
      (node (ref "IC2") (pin "P6") (pinfunction "AGND_P6") (pintype "power_in"))
      (node (ref "IC2") (pin "P7") (pinfunction "AGND_P7") (pintype "power_in"))
      (node (ref "IC2") (pin "R2") (pinfunction "AGND_R2") (pintype "power_in"))
      (node (ref "IC2") (pin "R3") (pinfunction "AGND_R3") (pintype "power_in"))
      (node (ref "IC2") (pin "R4") (pinfunction "AGND_R4") (pintype "power_in"))
      (node (ref "IC2") (pin "R5") (pinfunction "AGND_R5") (pintype "power_in"))
      (node (ref "IC2") (pin "R6") (pinfunction "AGND_R6") (pintype "power_in"))
      (node (ref "IC2") (pin "R7") (pinfunction "AGND_R7") (pintype "power_in"))
      (node (ref "IC2") (pin "T1") (pinfunction "AGND_T1") (pintype "power_in"))
      (node (ref "IC2") (pin "T15") (pinfunction "DGND_T15") (pintype "power_in"))
      (node (ref "IC2") (pin "T16") (pinfunction "DGND_T16") (pintype "power_in"))
      (node (ref "IC2") (pin "T2") (pinfunction "AGND_T2") (pintype "power_in"))
      (node (ref "IC2") (pin "T3") (pinfunction "AGND_T3") (pintype "power_in"))
      (node (ref "IC2") (pin "T6") (pinfunction "AGND_T6") (pintype "power_in"))
      (node (ref "IC2") (pin "T7") (pinfunction "AGND_T7") (pintype "power_in"))
      (node (ref "IC5") (pin "4") (pinfunction "GND_4") (pintype "power_in"))
      (node (ref "IC5") (pin "9") (pinfunction "EP_9") (pintype "power_in"))
      (node (ref "IC6") (pin "4") (pinfunction "GND_4") (pintype "power_in"))
      (node (ref "IC6") (pin "9") (pinfunction "EP_9") (pintype "power_in"))
      (node (ref "R22") (pin "1") (pinfunction "1_1") (pintype "passive"))
      (node (ref "R25") (pin "1") (pinfunction "1_1") (pintype "passive"))
      (node (ref "R26") (pin "1") (pinfunction "1_1") (pintype "passive"))
    )
    (net (code "2") (name "Net-(C86-Pad2)") (class "Default")
      (node (ref "C86") (pin "2") (pinfunction "2_2") (pintype "passive"))
      (node (ref "C87") (pin "2") (pinfunction "2_2") (pintype "passive"))
      (node (ref "C88") (pin "2") (pinfunction "2_2") (pintype "passive"))
      (node (ref "IC5") (pin "1") (pinfunction "OUT_1") (pintype "power_in"))
      (node (ref "IC5") (pin "2") (pinfunction "OUT_2") (pintype "power_in"))
      (node (ref "L4") (pin "1") (pinfunction "1_1") (pintype "passive"))
      (node (ref "R21") (pin "2") (pinfunction "2_2") (pintype "passive"))
    )
    (net (code "3") (name "Net-(C91-Pad2)") (class "Default")
      (node (ref "C91") (pin "2") (pinfunction "2_2") (pintype "passive"))
      (node (ref "C92") (pin "2") (pinfunction "2_2") (pintype "passive"))
      (node (ref "C93") (pin "2") (pinfunction "2_2") (pintype "passive"))
      (node (ref "IC6") (pin "1") (pinfunction "OUT_1") (pintype "power_in"))
      (node (ref "IC6") (pin "2") (pinfunction "OUT_2") (pintype "power_in"))
      (node (ref "L5") (pin "1") (pinfunction "1_1") (pintype "passive"))
      (node (ref "L6") (pin "1") (pinfunction "1_1") (pintype "passive"))
      (node (ref "R23") (pin "2") (pinfunction "2_2") (pintype "passive"))
    )
    (net (code "4") (name "Net-(C94-Pad2)") (class "Default")
      (node (ref "C94") (pin "2") (pinfunction "2_2") (pintype "passive"))
      (node (ref "IC6") (pin "7") (pinfunction "IN_7") (pintype "input"))
      (node (ref "IC6") (pin "8") (pinfunction "IN_8") (pintype "input"))
      (node (ref "L38") (pin "2") (pinfunction "2_2") (pintype "passive"))
    )
    (net (code "5") (name "Net-(IC5-EN)") (class "Default")
      (node (ref "C89") (pin "2") (pinfunction "2_2") (pintype "passive"))
      (node (ref "IC5") (pin "5") (pinfunction "EN_5") (pintype "input"))
      (node (ref "IC5") (pin "7") (pinfunction "IN_7") (pintype "input"))
      (node (ref "IC5") (pin "8") (pinfunction "IN_8") (pintype "input"))
      (node (ref "L37") (pin "2") (pinfunction "2_2") (pintype "passive"))
    )
    (net (code "6") (name "Net-(IC5-FB)") (class "Default")
      (node (ref "C86") (pin "1") (pinfunction "1_1") (pintype "passive"))
      (node (ref "IC5") (pin "3") (pinfunction "FB_3") (pintype "input"))
      (node (ref "R21") (pin "1") (pinfunction "1_1") (pintype "passive"))
      (node (ref "R22") (pin "2") (pinfunction "2_2") (pintype "passive"))
    )
    (net (code "7") (name "Net-(IC5-NR)") (class "Default")
      (node (ref "C90") (pin "2") (pinfunction "2_2") (pintype "passive"))
      (node (ref "IC5") (pin "6") (pinfunction "NR_6") (pintype "passive"))
    )
    (net (code "8") (name "Net-(IC6-EN)") (class "Default")
      (node (ref "IC6") (pin "5") (pinfunction "EN_5") (pintype "input"))
      (node (ref "R24") (pin "2") (pinfunction "2_2") (pintype "passive"))
      (node (ref "R26") (pin "2") (pinfunction "2_2") (pintype "passive"))
    )
    (net (code "9") (name "Net-(IC6-FB)") (class "Default")
      (node (ref "C91") (pin "1") (pinfunction "1_1") (pintype "passive"))
      (node (ref "IC6") (pin "3") (pinfunction "FB_3") (pintype "input"))
      (node (ref "R23") (pin "1") (pinfunction "1_1") (pintype "passive"))
      (node (ref "R25") (pin "2") (pinfunction "2_2") (pintype "passive"))
    )
    (net (code "10") (name "Net-(IC6-NR)") (class "Default")
      (node (ref "C95") (pin "2") (pinfunction "2_2") (pintype "passive"))
      (node (ref "IC6") (pin "6") (pinfunction "NR_6") (pintype "passive"))
    )
    (net (code "11") (name "P1V8") (class "Default")
      (node (ref "C65") (pin "2") (pinfunction "2_2") (pintype "passive"))
      (node (ref "C66") (pin "2") (pinfunction "2_2") (pintype "passive"))
      (node (ref "C67") (pin "2") (pinfunction "2_2") (pintype "passive"))
      (node (ref "C68") (pin "2") (pinfunction "2_2") (pintype "passive"))
      (node (ref "C69") (pin "2") (pinfunction "2_2") (pintype "passive"))
      (node (ref "C70") (pin "2") (pinfunction "2_2") (pintype "passive"))
      (node (ref "C71") (pin "2") (pinfunction "2_2") (pintype "passive"))
      (node (ref "C72") (pin "2") (pinfunction "2_2") (pintype "passive"))
      (node (ref "C73") (pin "2") (pinfunction "2_2") (pintype "passive"))
      (node (ref "C74") (pin "2") (pinfunction "2_2") (pintype "passive"))
      (node (ref "C75") (pin "2") (pinfunction "2_2") (pintype "passive"))
      (node (ref "C76") (pin "2") (pinfunction "2_2") (pintype "passive"))
      (node (ref "C77") (pin "2") (pinfunction "2_2") (pintype "passive"))
      (node (ref "IC2") (pin "G11") (pinfunction "VLVDS_G11") (pintype "power_in"))
      (node (ref "IC2") (pin "G12") (pinfunction "VLVDS_G12") (pintype "power_in"))
      (node (ref "IC2") (pin "H11") (pinfunction "VLVDS_H11") (pintype "power_in"))
      (node (ref "IC2") (pin "H12") (pinfunction "VLVDS_H12") (pintype "power_in"))
      (node (ref "IC2") (pin "H13") (pinfunction "VLVDS_H13") (pintype "power_in"))
      (node (ref "IC2") (pin "J11") (pinfunction "VLVDS_J11") (pintype "power_in"))
      (node (ref "IC2") (pin "J12") (pinfunction "VLVDS_J12") (pintype "power_in"))
      (node (ref "IC2") (pin "J13") (pinfunction "VLVDS_J13") (pintype "power_in"))
      (node (ref "IC2") (pin "K11") (pinfunction "VLVDS_K11") (pintype "power_in"))
      (node (ref "IC2") (pin "K12") (pinfunction "VLVDS_K12") (pintype "power_in"))
    )
    (net (code "12") (name "P1V8A") (class "Default")
      (node (ref "C198") (pin "2") (pinfunction "2_2") (pintype "passive"))
      (node (ref "L38") (pin "1") (pinfunction "1_1") (pintype "passive"))
    )
    (net (code "13") (name "P2V5") (class "Default")
      (node (ref "C197") (pin "2") (pinfunction "2_2") (pintype "passive"))
      (node (ref "L37") (pin "1") (pinfunction "1_1") (pintype "passive"))
    )
    (net (code "14") (name "VA_1V1") (class "Default")
      (node (ref "C26") (pin "2") (pinfunction "2_2") (pintype "passive"))
      (node (ref "C27") (pin "2") (pinfunction "2_2") (pintype "passive"))
      (node (ref "C28") (pin "2") (pinfunction "2_2") (pintype "passive"))
      (node (ref "C29") (pin "2") (pinfunction "2_2") (pintype "passive"))
      (node (ref "C30") (pin "2") (pinfunction "2_2") (pintype "passive"))
      (node (ref "C31") (pin "2") (pinfunction "2_2") (pintype "passive"))
      (node (ref "C32") (pin "2") (pinfunction "2_2") (pintype "passive"))
      (node (ref "C33") (pin "2") (pinfunction "2_2") (pintype "passive"))
      (node (ref "C34") (pin "2") (pinfunction "2_2") (pintype "passive"))
      (node (ref "C35") (pin "2") (pinfunction "2_2") (pintype "passive"))
      (node (ref "C36") (pin "2") (pinfunction "2_2") (pintype "passive"))
      (node (ref "C37") (pin "2") (pinfunction "2_2") (pintype "passive"))
      (node (ref "C38") (pin "2") (pinfunction "2_2") (pintype "passive"))
      (node (ref "C39") (pin "2") (pinfunction "2_2") (pintype "passive"))
      (node (ref "C40") (pin "2") (pinfunction "2_2") (pintype "passive"))
      (node (ref "C41") (pin "2") (pinfunction "2_2") (pintype "passive"))
      (node (ref "C42") (pin "2") (pinfunction "2_2") (pintype "passive"))
      (node (ref "C43") (pin "2") (pinfunction "2_2") (pintype "passive"))
      (node (ref "C44") (pin "2") (pinfunction "2_2") (pintype "passive"))
      (node (ref "IC2") (pin "E4") (pinfunction "VA11_E4") (pintype "power_in"))
      (node (ref "IC2") (pin "E5") (pinfunction "VA11_E5") (pintype "power_in"))
      (node (ref "IC2") (pin "E6") (pinfunction "VA11_E6") (pintype "power_in"))
      (node (ref "IC2") (pin "F3") (pinfunction "VA11_F3") (pintype "power_in"))
      (node (ref "IC2") (pin "F4") (pinfunction "VA11_F4") (pintype "power_in"))
      (node (ref "IC2") (pin "F5") (pinfunction "VA11_F5") (pintype "power_in"))
      (node (ref "IC2") (pin "F6") (pinfunction "VA11_F6") (pintype "power_in"))
      (node (ref "IC2") (pin "L3") (pinfunction "VA11_L3") (pintype "power_in"))
      (node (ref "IC2") (pin "L4") (pinfunction "VA11_L4") (pintype "power_in"))
      (node (ref "IC2") (pin "L5") (pinfunction "VA11_L5") (pintype "power_in"))
      (node (ref "IC2") (pin "L6") (pinfunction "VA11_L6") (pintype "power_in"))
      (node (ref "IC2") (pin "M4") (pinfunction "VA11_M4") (pintype "power_in"))
      (node (ref "IC2") (pin "M5") (pinfunction "VA11_M5") (pintype "power_in"))
      (node (ref "IC2") (pin "M6") (pinfunction "VA11_M6") (pintype "power_in"))
      (node (ref "L5") (pin "2") (pinfunction "2_2") (pintype "passive"))
    )
    (net (code "15") (name "VA_1V9") (class "Default")
      (node (ref "C45") (pin "2") (pinfunction "2_2") (pintype "passive"))
      (node (ref "C46") (pin "2") (pinfunction "2_2") (pintype "passive"))
      (node (ref "C47") (pin "2") (pinfunction "2_2") (pintype "passive"))
      (node (ref "C48") (pin "2") (pinfunction "2_2") (pintype "passive"))
      (node (ref "C49") (pin "2") (pinfunction "2_2") (pintype "passive"))
      (node (ref "C50") (pin "2") (pinfunction "2_2") (pintype "passive"))
      (node (ref "C51") (pin "2") (pinfunction "2_2") (pintype "passive"))
      (node (ref "C52") (pin "2") (pinfunction "2_2") (pintype "passive"))
      (node (ref "C53") (pin "2") (pinfunction "2_2") (pintype "passive"))
      (node (ref "C54") (pin "2") (pinfunction "2_2") (pintype "passive"))
      (node (ref "C55") (pin "2") (pinfunction "2_2") (pintype "passive"))
      (node (ref "C56") (pin "2") (pinfunction "2_2") (pintype "passive"))
      (node (ref "C57") (pin "2") (pinfunction "2_2") (pintype "passive"))
      (node (ref "C58") (pin "2") (pinfunction "2_2") (pintype "passive"))
      (node (ref "C59") (pin "2") (pinfunction "2_2") (pintype "passive"))
      (node (ref "C60") (pin "2") (pinfunction "2_2") (pintype "passive"))
      (node (ref "C61") (pin "2") (pinfunction "2_2") (pintype "passive"))
      (node (ref "C62") (pin "2") (pinfunction "2_2") (pintype "passive"))
      (node (ref "C63") (pin "2") (pinfunction "2_2") (pintype "passive"))
      (node (ref "C64") (pin "2") (pinfunction "2_2") (pintype "passive"))
      (node (ref "IC2") (pin "G3") (pinfunction "VA19_G3") (pintype "power_in"))
      (node (ref "IC2") (pin "G4") (pinfunction "VA19_G4") (pintype "power_in"))
      (node (ref "IC2") (pin "G5") (pinfunction "VA19_G5") (pintype "power_in"))
      (node (ref "IC2") (pin "G6") (pinfunction "VA19_G6") (pintype "power_in"))
      (node (ref "IC2") (pin "H3") (pinfunction "VA19_H3") (pintype "power_in"))
      (node (ref "IC2") (pin "H4") (pinfunction "VA19_H4") (pintype "power_in"))
      (node (ref "IC2") (pin "H5") (pinfunction "VA19_H5") (pintype "power_in"))
      (node (ref "IC2") (pin "H6") (pinfunction "VA19_H6") (pintype "power_in"))
      (node (ref "IC2") (pin "J3") (pinfunction "VA19_J3") (pintype "power_in"))
      (node (ref "IC2") (pin "J4") (pinfunction "VA19_J4") (pintype "power_in"))
      (node (ref "IC2") (pin "J5") (pinfunction "VA19_J5") (pintype "power_in"))
      (node (ref "IC2") (pin "J6") (pinfunction "VA19_J6") (pintype "power_in"))
      (node (ref "IC2") (pin "K3") (pinfunction "VA19_K3") (pintype "power_in"))
      (node (ref "IC2") (pin "K4") (pinfunction "VA19_K4") (pintype "power_in"))
      (node (ref "IC2") (pin "K5") (pinfunction "VA19_K5") (pintype "power_in"))
      (node (ref "IC2") (pin "K6") (pinfunction "VA19_K6") (pintype "power_in"))
      (node (ref "L4") (pin "2") (pinfunction "2_2") (pintype "passive"))
      (node (ref "R24") (pin "1") (pinfunction "1_1") (pintype "passive"))
    )
    (net (code "16") (name "VD_1V1") (class "Default")
      (node (ref "C78") (pin "2") (pinfunction "2_2") (pintype "passive"))
      (node (ref "C79") (pin "2") (pinfunction "2_2") (pintype "passive"))
      (node (ref "C80") (pin "2") (pinfunction "2_2") (pintype "passive"))
      (node (ref "C81") (pin "2") (pinfunction "2_2") (pintype "passive"))
      (node (ref "C82") (pin "2") (pinfunction "2_2") (pintype "passive"))
      (node (ref "C83") (pin "2") (pinfunction "2_2") (pintype "passive"))
      (node (ref "C84") (pin "2") (pinfunction "2_2") (pintype "passive"))
      (node (ref "C85") (pin "2") (pinfunction "2_2") (pintype "passive"))
      (node (ref "IC2") (pin "E8") (pinfunction "VD11_E8") (pintype "power_in"))
      (node (ref "IC2") (pin "F8") (pinfunction "VD11_F8") (pintype "power_in"))
      (node (ref "IC2") (pin "G8") (pinfunction "VD11_G8") (pintype "power_in"))
      (node (ref "IC2") (pin "K8") (pinfunction "VD11_K8") (pintype "power_in"))
      (node (ref "IC2") (pin "L8") (pinfunction "VD11_L8") (pintype "power_in"))
      (node (ref "IC2") (pin "M8") (pinfunction "VD11_M8") (pintype "power_in"))
      (node (ref "L6") (pin "2") (pinfunction "2_2") (pintype "passive"))
    )
  )
)
